# MEMORIA.net
KiCad netlist of a schematic drawn in Altium Designer
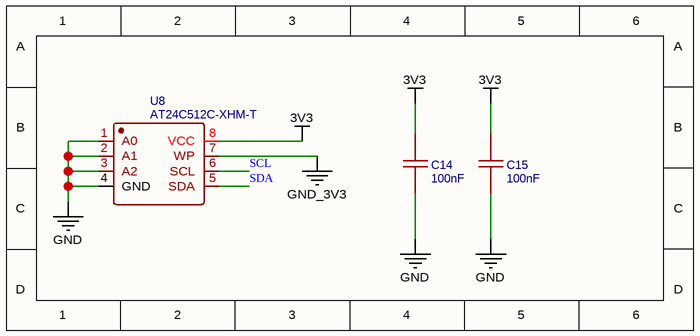
[diagram p0: MEMORIA.schdoc]

(export (version "E")
  (design (tool "Eeschema 10.0.6"))
  (components
    (comp (ref "C14")
      (value "100nF")
      (fields
        (field (name "BOM_SUPPLIER PART") "C49678")
        (field (name "BOM_MANUFACTURER PART") "CC0805KRX7R9BB104")
        (field (name "CONTRIBUTOR") "LCEDA_Lib")
      )
      (libsource (lib "altium-import") (part "root_1_100nF_"))
    )
    (comp (ref "C15")
      (value "100nF")
      (fields
        (field (name "BOM_SUPPLIER PART") "C49678")
        (field (name "BOM_MANUFACTURER PART") "CC0805KRX7R9BB104")
        (field (name "CONTRIBUTOR") "LCEDA_Lib")
      )
      (libsource (lib "altium-import") (part "root_1_100nF_"))
    )
    (comp (ref "U8")
      (value "AT24C512C-XHM-T")
      (fields (field (name "BOM_SUPPLIER PART") "C111546"))
      (libsource (lib "altium-import") (part "root_0_AT24C512C-XHM-T_"))
    )
  )
  (nets
    (net (code "1") (name "/SCL") (class "Default")
      (node (ref "U8") (pin "6") (pinfunction "SCL_6") (pintype "passive"))
    )
    (net (code "2") (name "/SDA") (class "Default")
      (node (ref "U8") (pin "5") (pinfunction "SDA_5") (pintype "passive"))
    )
    (net (code "3") (name "3V3") (class "Default")
      (node (ref "C14") (pin "2") (pinfunction "2_2") (pintype "passive"))
      (node (ref "C15") (pin "2") (pinfunction "2_2") (pintype "passive"))
      (node (ref "U8") (pin "8") (pinfunction "VCC_8") (pintype "passive"))
    )
    (net (code "4") (name "GND") (class "Default")
      (node (ref "C14") (pin "1") (pinfunction "1_1") (pintype "passive"))
      (node (ref "C15") (pin "1") (pinfunction "1_1") (pintype "passive"))
      (node (ref "U8") (pin "1") (pinfunction "A0_1") (pintype "passive"))
      (node (ref "U8") (pin "2") (pinfunction "A1_2") (pintype "passive"))
      (node (ref "U8") (pin "3") (pinfunction "A2_3") (pintype "passive"))
      (node (ref "U8") (pin "4") (pinfunction "GND_4") (pintype "passive"))
    )
    (net (code "5") (name "GND_3V3") (class "Default")
      (node (ref "U8") (pin "7") (pinfunction "WP_7") (pintype "passive"))
    )
  )
)
